# main.net
KiCad netlist of a schematic drawn in Altium Designer
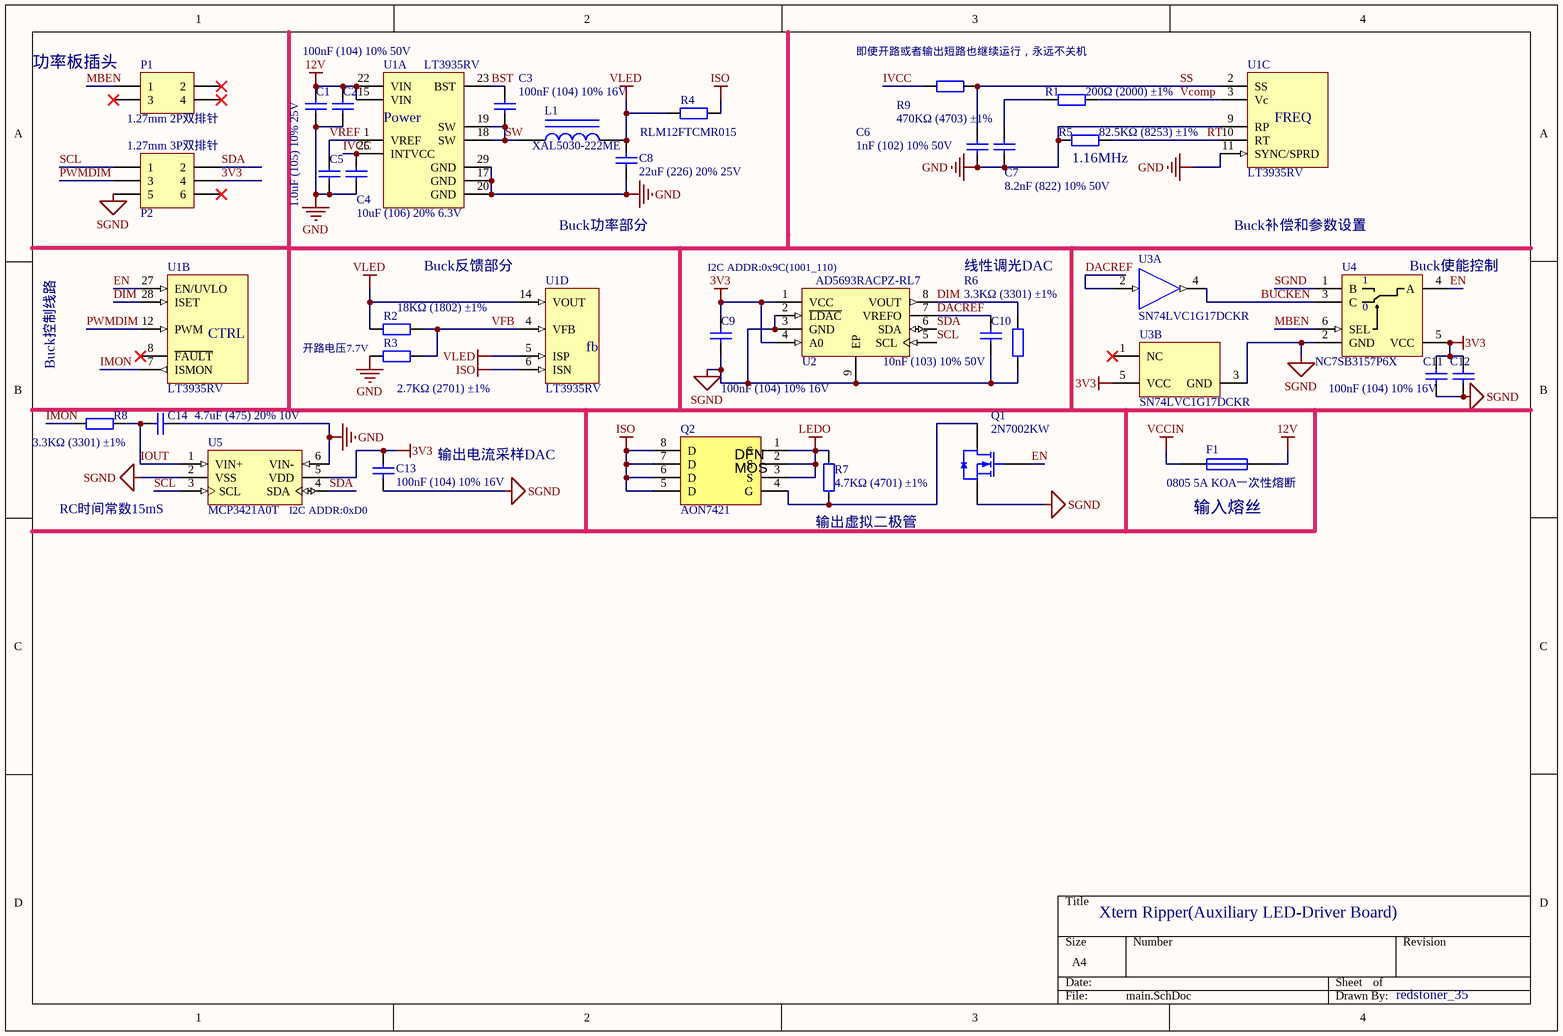
[diagram p0: main.SchDoc]

(export (version "E")
  (design (tool "Eeschema 10.0.6"))
  (components
    (comp (ref "C1")
      (value "100nF (104) 10% 50V")
      (footprint "0603_C")
      (description "贴片电容")
      (libsource (lib "Miscellaneous Devices LC") (part "0603 100nF (104) 10% 50V"))
    )
    (comp (ref "C2")
      (value "100nF (104) 10% 50V")
      (footprint "0603_C")
      (description "贴片电容")
      (libsource (lib "Miscellaneous Devices LC") (part "0603 100nF (104) 10% 50V"))
    )
    (comp (ref "C3")
      (value "100nF (104) 10% 16V")
      (footprint "0402_C")
      (description "贴片电容")
      (libsource (lib "Miscellaneous Devices LC") (part "0402 100nF (104) 10% 16V"))
    )
    (comp (ref "C4")
      (value "10uF (106) 20% 6.3V")
      (footprint "0402_C")
      (description "贴片电容")
      (libsource (lib "Miscellaneous Devices LC") (part "0402 10uF (106) 20% 6.3V"))
    )
    (comp (ref "C5")
      (value "1.0uF (105) 10% 25V")
      (footprint "0402_C")
      (description "贴片电容")
      (libsource (lib "Miscellaneous Devices LC") (part "0402 1.0uF (105) 10% 25V"))
    )
    (comp (ref "C6")
      (value "1nF (102) 10% 50V")
      (footprint "0402_C")
      (description "贴片电容")
      (libsource (lib "Miscellaneous Devices LC") (part "0402 1nF (102) 10% 50V"))
    )
    (comp (ref "C7")
      (value "8.2nF (822) 10% 50V")
      (footprint "0402_C")
      (description "贴片电容")
      (libsource (lib "Miscellaneous Devices LC") (part "0402 2.2nF (222) 10% 50V"))
    )
    (comp (ref "C8")
      (value "22uF (226) 20% 25V")
      (footprint "0805_C")
      (description "贴片电容")
      (libsource (lib "Miscellaneous Devices LC") (part "0805 22uF (226) 20% 25V"))
    )
    (comp (ref "C9")
      (value "100nF (104) 10% 16V")
      (footprint "0402_C")
      (description "贴片电容")
      (libsource (lib "Miscellaneous Devices LC") (part "0402 100nF (104) 10% 16V"))
    )
    (comp (ref "C10")
      (value "10nF (103) 10% 50V")
      (footprint "0402_C")
      (description "贴片电容")
      (libsource (lib "Miscellaneous Devices LC") (part "0402 10nF (103) 10% 50V"))
    )
    (comp (ref "C11")
      (value "100nF (104) 10% 16V")
      (footprint "0402_C")
      (description "贴片电容")
      (libsource (lib "Miscellaneous Devices LC") (part "0402 100nF (104) 10% 16V"))
    )
    (comp (ref "C12")
      (value "100nF (104) 10% 16V")
      (footprint "0402_C")
      (description "贴片电容")
      (libsource (lib "Miscellaneous Devices LC") (part "0402 100nF (104) 10% 16V"))
    )
    (comp (ref "C13")
      (value "100nF (104) 10% 16V")
      (footprint "0402_C")
      (description "贴片电容")
      (libsource (lib "Miscellaneous Devices LC") (part "0402 100nF (104) 10% 16V"))
    )
    (comp (ref "C14")
      (value "4.7uF (475) 20% 10V")
      (footprint "0402_C")
      (description "贴片电容")
      (libsource (lib "Miscellaneous Devices LC") (part "0402 4.7uF (475) 20% 10V"))
    )
    (comp (ref "F1")
      (value "0805 5A KOA一次性熔断")
      (footprint "FU 0805")
      (description "Fuse")
      (fields (field (name "PUBLISHER") "Altium Limited"))
      (libsource (lib "Miscellaneous Devices") (part "Fuse 1"))
    )
    (comp (ref "L1")
      (value "XAL5030-222ME")
      (footprint "FEXL0520A-***M")
      (description "Magnetic-Core Inductor")
      (fields (field (name "PUBLISHER") "Altium Limited"))
      (libsource (lib "Miscellaneous Devices") (part "Inductor Iron"))
    )
    (comp (ref "P1")
      (value "1.27mm 2P双排针")
      (footprint "MHDR2X2")
      (description "Header, 2-Pin, Dual row")
      (fields (field (name "PUBLISHER") "Altium Limited"))
      (libsource (lib "Miscellaneous Connectors") (part "MHDR2X2"))
    )
    (comp (ref "P2")
      (value "1.27mm 3P双排针")
      (footprint "MHDR2X3")
      (description "Header, 3-Pin, Dual row")
      (fields (field (name "PUBLISHER") "Altium Limited"))
      (libsource (lib "Miscellaneous Connectors") (part "MHDR2X3"))
    )
    (comp (ref "Q1")
      (value "2N7002KW")
      (footprint "SC70-3")
      (description "MOS(场效应管)")
      (libsource (lib "Miscellaneous Devices LC") (part "2N7002 7002"))
    )
    (comp (ref "Q2")
      (value "AON7421")
      (footprint "DFN-8_L3.0-W3.0-P0.65-BL")
      (description "PDFN3x3 -20V -50A 5.8mΩ P-Ch MOSFET")
      (libsource (lib "custom") (part "SON/DFN5x6 MOS"))
    )
    (comp (ref "R1")
      (value "200Ω (2000) ±1%")
      (footprint "0402_R")
      (description "贴片电阻")
      (libsource (lib "") (part "0402 10KΩ (1002) 1%_1"))
    )
    (comp (ref "R2")
      (value "18KΩ (1802) ±1%")
      (footprint "0402_R")
      (description "贴片电阻")
      (libsource (lib "") (part "0402 10KΩ (1002) 1%_1"))
    )
    (comp (ref "R3")
      (value "2.7KΩ (2701) ±1%")
      (footprint "0402_R")
      (description "贴片电阻")
      (libsource (lib "Miscellaneous Devices LC") (part "0402 10KΩ (1002) 1%"))
    )
    (comp (ref "R4")
      (value "RLM12FTCMR015")
      (footprint "1206_R")
      (description "贴片合金检流电阻 15mΩ (R015) ±1% 1206 1W")
      (libsource (lib "Miscellaneous Devices LC") (part "1206 0Ω (0R0) 1%"))
    )
    (comp (ref "R5")
      (value "82.5KΩ (8253) ±1%")
      (footprint "0402_R")
      (description "贴片电阻")
      (libsource (lib "Miscellaneous Devices LC") (part "0402 1KΩ (1001) 1%"))
    )
    (comp (ref "R6")
      (value "3.3KΩ (3301) ±1%")
      (footprint "0402_R")
      (description "贴片电阻")
      (libsource (lib "") (part "0402 3.3KΩ (3301) 1%_1"))
    )
    (comp (ref "R7")
      (value "4.7KΩ (4701) ±1%")
      (footprint "0402_R")
      (description "贴片电阻")
      (libsource (lib "Miscellaneous Devices LC") (part "0402 4.7KΩ (4701) 1%"))
    )
    (comp (ref "R8")
      (value "3.3KΩ (3301) ±1%")
      (footprint "0402_R")
      (description "贴片电阻")
      (libsource (lib "Miscellaneous Devices LC") (part "0402 3.3KΩ (3301) 1%"))
    )
    (comp (ref "R9")
      (value "470KΩ (4703) ±1%")
      (footprint "0402_R")
      (description "贴片电阻")
      (libsource (lib "Miscellaneous Devices LC") (part "0402 470KΩ (4703) 1%"))
    )
    (comp (ref "U1")
      (value "LT3935RV")
      (footprint "LQFN-28")
      (description "36V 4A Synchronous Buck LED Driver")
      (libsource (lib "custom") (part "LT3935RV"))
    )
    (comp (ref "U2")
      (value "AD5693RACPZ-RL7")
      (footprint "LFCSP-8-10")
      (description "16bit I2C Nano DAC with 2.5V internal Ref in 2x2mm SON")
      (libsource (lib "custom") (part "AD5693RACPZ-RL7"))
    )
    (comp (ref "U3")
      (value "SN74LVC1G17DCKR")
      (footprint "DCK0005A_N")
      (description "Single Schmitt-Trigger Buffer, DCK0005A, LARGE T&R")
      (fields
        (field (name "GENERIC PART NUMBER") "SN74LVC1G17")
        (field (name "MANUFACTURER") "Texas Instruments")
      )
      (libsource (lib "TI_Logic_Little_Logic") (part "SN74LVC1G17DCKR"))
    )
    (comp (ref "U4")
      (value "NC7SB3157P6X")
      (footprint "SC70-6")
      (description "Low-Voltage Analog Switch SPDT,1.8-5V Power")
      (libsource (lib "custom") (part "NC7SB3157P6X"))
    )
    (comp (ref "U5")
      (value "MCP3421A0T")
      (footprint "SOT95P245X110-6N")
      (description "I2C差分输入ADC，18位 240SPS")
      (libsource (lib "custom") (part "MCP3421"))
    )
  )
  (nets
    (net (code "1") (name "/BST") (class "Default")
      (node (ref "C3") (pin "2") (pinfunction "2_2") (pintype "passive"))
      (node (ref "U1") (pin "23") (pinfunction "BST_23") (pintype "power_in"))
    )
    (net (code "2") (name "/BUCKEN") (class "Default")
      (node (ref "U3") (pin "4") (pinfunction "Y_4") (pintype "output"))
      (node (ref "U4") (pin "3") (pinfunction "C_3") (pintype "passive"))
    )
    (net (code "3") (name "/DACREF") (class "Default")
      (node (ref "C10") (pin "2") (pinfunction "2_2") (pintype "passive"))
      (node (ref "U2") (pin "7") (pinfunction "VREFO_7") (pintype "passive"))
      (node (ref "U3") (pin "2") (pinfunction "A_2") (pintype "input"))
    )
    (net (code "4") (name "/DIM") (class "Default")
      (node (ref "R6") (pin "2") (pinfunction "2_2") (pintype "passive"))
      (node (ref "U1") (pin "28") (pinfunction "ISET_28") (pintype "input"))
      (node (ref "U2") (pin "8") (pinfunction "VOUT_8") (pintype "output"))
    )
    (net (code "5") (name "/EN") (class "Default")
      (node (ref "Q1") (pin "1") (pinfunction "G_1") (pintype "passive"))
      (node (ref "U1") (pin "27") (pinfunction "EN/UVLO_27") (pintype "input"))
      (node (ref "U4") (pin "4") (pinfunction "A_4") (pintype "passive"))
    )
    (net (code "6") (name "/IMON") (class "Default")
      (node (ref "R8") (pin "1") (pinfunction "1_1") (pintype "passive"))
      (node (ref "U1") (pin "7") (pinfunction "ISMON_7") (pintype "output"))
    )
    (net (code "7") (name "/IOUT") (class "Default")
      (node (ref "C14") (pin "1") (pinfunction "1_1") (pintype "passive"))
      (node (ref "R8") (pin "2") (pinfunction "2_2") (pintype "passive"))
      (node (ref "U5") (pin "1") (pinfunction "VIN+_1") (pintype "input"))
    )
    (net (code "8") (name "/IVCC") (class "Default")
      (node (ref "C4") (pin "2") (pinfunction "2_2") (pintype "passive"))
      (node (ref "R9") (pin "1") (pinfunction "1_1") (pintype "passive"))
      (node (ref "U1") (pin "25") (pinfunction "INTVCC_25") (pintype "power_in"))
    )
    (net (code "9") (name "/MBEN") (class "Default")
      (node (ref "P1") (pin "1") (pinfunction "1_1") (pintype "passive"))
      (node (ref "U4") (pin "6") (pinfunction "SEL_6") (pintype "input"))
    )
    (net (code "10") (name "/PWMDIM") (class "Default")
      (node (ref "P2") (pin "3") (pinfunction "3_3") (pintype "passive"))
      (node (ref "U1") (pin "12") (pinfunction "PWM_12") (pintype "input"))
    )
    (net (code "11") (name "/RT") (class "Default")
      (node (ref "R5") (pin "2") (pinfunction "2_2") (pintype "passive"))
      (node (ref "U1") (pin "10") (pinfunction "RT_10") (pintype "passive"))
    )
    (net (code "12") (name "/SCL") (class "Default")
      (node (ref "P2") (pin "1") (pinfunction "1_1") (pintype "passive"))
      (node (ref "U2") (pin "5") (pinfunction "SCL_5") (pintype "input"))
      (node (ref "U5") (pin "3") (pinfunction "SCL_3") (pintype "input"))
    )
    (net (code "13") (name "/SDA") (class "Default")
      (node (ref "P2") (pin "2") (pinfunction "2_2") (pintype "passive"))
      (node (ref "U2") (pin "6") (pinfunction "SDA_6") (pintype "bidirectional"))
      (node (ref "U5") (pin "4") (pinfunction "SDA_4") (pintype "bidirectional"))
    )
    (net (code "14") (name "/SS") (class "Default")
      (node (ref "C6") (pin "2") (pinfunction "2_2") (pintype "passive"))
      (node (ref "R9") (pin "2") (pinfunction "2_2") (pintype "passive"))
      (node (ref "U1") (pin "2") (pinfunction "SS_2") (pintype "passive"))
    )
    (net (code "15") (name "/SW") (class "Default")
      (node (ref "C3") (pin "1") (pinfunction "1_1") (pintype "passive"))
      (node (ref "L1") (pin "1") (pinfunction "1_1") (pintype "passive"))
      (node (ref "U1") (pin "18") (pinfunction "SW_18") (pintype "power_in"))
      (node (ref "U1") (pin "19") (pinfunction "SW_19") (pintype "power_in"))
    )
    (net (code "16") (name "/VFB") (class "Default")
      (node (ref "R2") (pin "2") (pinfunction "2_2") (pintype "passive"))
      (node (ref "R3") (pin "1") (pinfunction "1_1") (pintype "passive"))
      (node (ref "U1") (pin "4") (pinfunction "VFB_4") (pintype "input"))
    )
    (net (code "17") (name "/VREF") (class "Default")
      (node (ref "C5") (pin "2") (pinfunction "2_2") (pintype "passive"))
      (node (ref "U1") (pin "1") (pinfunction "VREF_1") (pintype "power_in"))
    )
    (net (code "18") (name "/Vcomp") (class "Default")
      (node (ref "R1") (pin "2") (pinfunction "2_2") (pintype "passive"))
      (node (ref "U1") (pin "3") (pinfunction "Vc_3") (pintype "passive"))
    )
    (net (code "19") (name "3V3") (class "Default")
      (node (ref "C11") (pin "2") (pinfunction "2_2") (pintype "passive"))
      (node (ref "C12") (pin "2") (pinfunction "2_2") (pintype "passive"))
      (node (ref "C13") (pin "2") (pinfunction "2_2") (pintype "passive"))
      (node (ref "C9") (pin "2") (pinfunction "2_2") (pintype "passive"))
      (node (ref "P2") (pin "4") (pinfunction "4_4") (pintype "passive"))
      (node (ref "U2") (pin "1") (pinfunction "VCC_1") (pintype "power_in"))
      (node (ref "U2") (pin "4") (pinfunction "A0_4") (pintype "input"))
      (node (ref "U3") (pin "5") (pinfunction "VCC_5") (pintype "power_in"))
      (node (ref "U4") (pin "5") (pinfunction "VCC_5") (pintype "power_in"))
      (node (ref "U5") (pin "5") (pinfunction "VDD_5") (pintype "power_in"))
    )
    (net (code "20") (name "12V") (class "Default")
      (node (ref "C1") (pin "2") (pinfunction "2_2") (pintype "passive"))
      (node (ref "C2") (pin "2") (pinfunction "2_2") (pintype "passive"))
      (node (ref "F1") (pin "2") (pinfunction "2_2") (pintype "passive"))
      (node (ref "U1") (pin "15") (pinfunction "VIN_15") (pintype "power_in"))
      (node (ref "U1") (pin "22") (pinfunction "VIN_22") (pintype "power_in"))
    )
    (net (code "21") (name "GND") (class "Default")
      (node (ref "C1") (pin "1") (pinfunction "1_1") (pintype "passive"))
      (node (ref "C14") (pin "2") (pinfunction "2_2") (pintype "passive"))
      (node (ref "C2") (pin "1") (pinfunction "1_1") (pintype "passive"))
      (node (ref "C4") (pin "1") (pinfunction "1_1") (pintype "passive"))
      (node (ref "C5") (pin "1") (pinfunction "1_1") (pintype "passive"))
      (node (ref "C6") (pin "1") (pinfunction "1_1") (pintype "passive"))
      (node (ref "C7") (pin "1") (pinfunction "1_1") (pintype "passive"))
      (node (ref "C8") (pin "1") (pinfunction "1_1") (pintype "passive"))
      (node (ref "R3") (pin "2") (pinfunction "2_2") (pintype "passive"))
      (node (ref "R5") (pin "1") (pinfunction "1_1") (pintype "passive"))
      (node (ref "U1") (pin "11") (pinfunction "SYNC/SPRD_11") (pintype "input"))
      (node (ref "U1") (pin "17") (pinfunction "GND_17") (pintype "power_in"))
      (node (ref "U1") (pin "20") (pinfunction "GND_20") (pintype "power_in"))
      (node (ref "U1") (pin "29") (pinfunction "GND_29") (pintype "power_in"))
      (node (ref "U1") (pin "9") (pinfunction "RP_9") (pintype "passive"))
      (node (ref "U5") (pin "6") (pinfunction "VIN-_6") (pintype "input"))
    )
    (net (code "22") (name "ISO") (class "Default")
      (node (ref "Q2") (pin "5") (pinfunction "D_5") (pintype "passive"))
      (node (ref "Q2") (pin "6") (pinfunction "D_6") (pintype "passive"))
      (node (ref "Q2") (pin "7") (pinfunction "D_7") (pintype "passive"))
      (node (ref "Q2") (pin "8") (pinfunction "D_8") (pintype "passive"))
      (node (ref "R4") (pin "2") (pinfunction "2_2") (pintype "passive"))
      (node (ref "U1") (pin "6") (pinfunction "ISN_6") (pintype "input"))
    )
    (net (code "23") (name "LEDO") (class "Default")
      (node (ref "Q2") (pin "1") (pinfunction "S_1") (pintype "passive"))
      (node (ref "Q2") (pin "2") (pinfunction "S_2") (pintype "passive"))
      (node (ref "Q2") (pin "3") (pinfunction "S_3") (pintype "passive"))
      (node (ref "R7") (pin "2") (pinfunction "2_2") (pintype "passive"))
    )
    (net (code "24") (name "Net-(C7-Pad2)") (class "Default")
      (node (ref "C7") (pin "2") (pinfunction "2_2") (pintype "passive"))
      (node (ref "R1") (pin "1") (pinfunction "1_1") (pintype "passive"))
    )
    (net (code "25") (name "Net-(Q1-D)") (class "Default")
      (node (ref "Q1") (pin "3") (pinfunction "D_3") (pintype "passive"))
      (node (ref "Q2") (pin "4") (pinfunction "G_4") (pintype "passive"))
      (node (ref "R7") (pin "1") (pinfunction "1_1") (pintype "passive"))
    )
    (net (code "26") (name "SGND") (class "Default")
      (node (ref "C10") (pin "1") (pinfunction "1_1") (pintype "passive"))
      (node (ref "C11") (pin "1") (pinfunction "1_1") (pintype "passive"))
      (node (ref "C12") (pin "1") (pinfunction "1_1") (pintype "passive"))
      (node (ref "C13") (pin "1") (pinfunction "1_1") (pintype "passive"))
      (node (ref "C9") (pin "1") (pinfunction "1_1") (pintype "passive"))
      (node (ref "P2") (pin "5") (pinfunction "5_5") (pintype "passive"))
      (node (ref "Q1") (pin "2") (pinfunction "S_2") (pintype "passive"))
      (node (ref "R6") (pin "1") (pinfunction "1_1") (pintype "passive"))
      (node (ref "U2") (pin "2") (pinfunction "~{LDAC}_2") (pintype "input"))
      (node (ref "U2") (pin "3") (pinfunction "GND_3") (pintype "power_in"))
      (node (ref "U2") (pin "9") (pinfunction "EP_9") (pintype "passive"))
      (node (ref "U3") (pin "3") (pinfunction "GND_3") (pintype "power_in"))
      (node (ref "U4") (pin "1") (pinfunction "B_1") (pintype "passive"))
      (node (ref "U4") (pin "2") (pinfunction "GND_2") (pintype "power_in"))
      (node (ref "U5") (pin "2") (pinfunction "VSS_2") (pintype "power_in"))
    )
    (net (code "27") (name "VCCIN") (class "Default")
      (node (ref "F1") (pin "1") (pinfunction "1_1") (pintype "passive"))
    )
    (net (code "28") (name "VLED") (class "Default")
      (node (ref "C8") (pin "2") (pinfunction "2_2") (pintype "passive"))
      (node (ref "L1") (pin "2") (pinfunction "2_2") (pintype "passive"))
      (node (ref "R2") (pin "1") (pinfunction "1_1") (pintype "passive"))
      (node (ref "R4") (pin "1") (pinfunction "1_1") (pintype "passive"))
      (node (ref "U1") (pin "14") (pinfunction "VOUT_14") (pintype "input"))
      (node (ref "U1") (pin "5") (pinfunction "ISP_5") (pintype "input"))
    )
    (net (code "29") (name "unconnected-(P1-Pad2)") (class "Default")
      (node (ref "P1") (pin "2") (pinfunction "2_2") (pintype "passive+no_connect"))
    )
    (net (code "30") (name "unconnected-(P1-Pad3)") (class "Default")
      (node (ref "P1") (pin "3") (pinfunction "3_3") (pintype "passive+no_connect"))
    )
    (net (code "31") (name "unconnected-(P1-Pad4)") (class "Default")
      (node (ref "P1") (pin "4") (pinfunction "4_4") (pintype "passive+no_connect"))
    )
    (net (code "32") (name "unconnected-(P2-Pad6)") (class "Default")
      (node (ref "P2") (pin "6") (pinfunction "6_6") (pintype "passive+no_connect"))
    )
    (net (code "33") (name "unconnected-(U1B-~{FAULT}-Pad8)") (class "Default")
      (node (ref "U1") (pin "8") (pinfunction "~{FAULT}_8") (pintype "open_collector+no_connect"))
    )
    (net (code "34") (name "unconnected-(U3B-NC-Pad1)") (class "Default")
      (node (ref "U3") (pin "1") (pinfunction "NC_1") (pintype "passive+no_connect"))
    )
  )
)
